# ZHSD-Power-Decoupling.net
KiCad netlist of a schematic drawn in Altium Designer
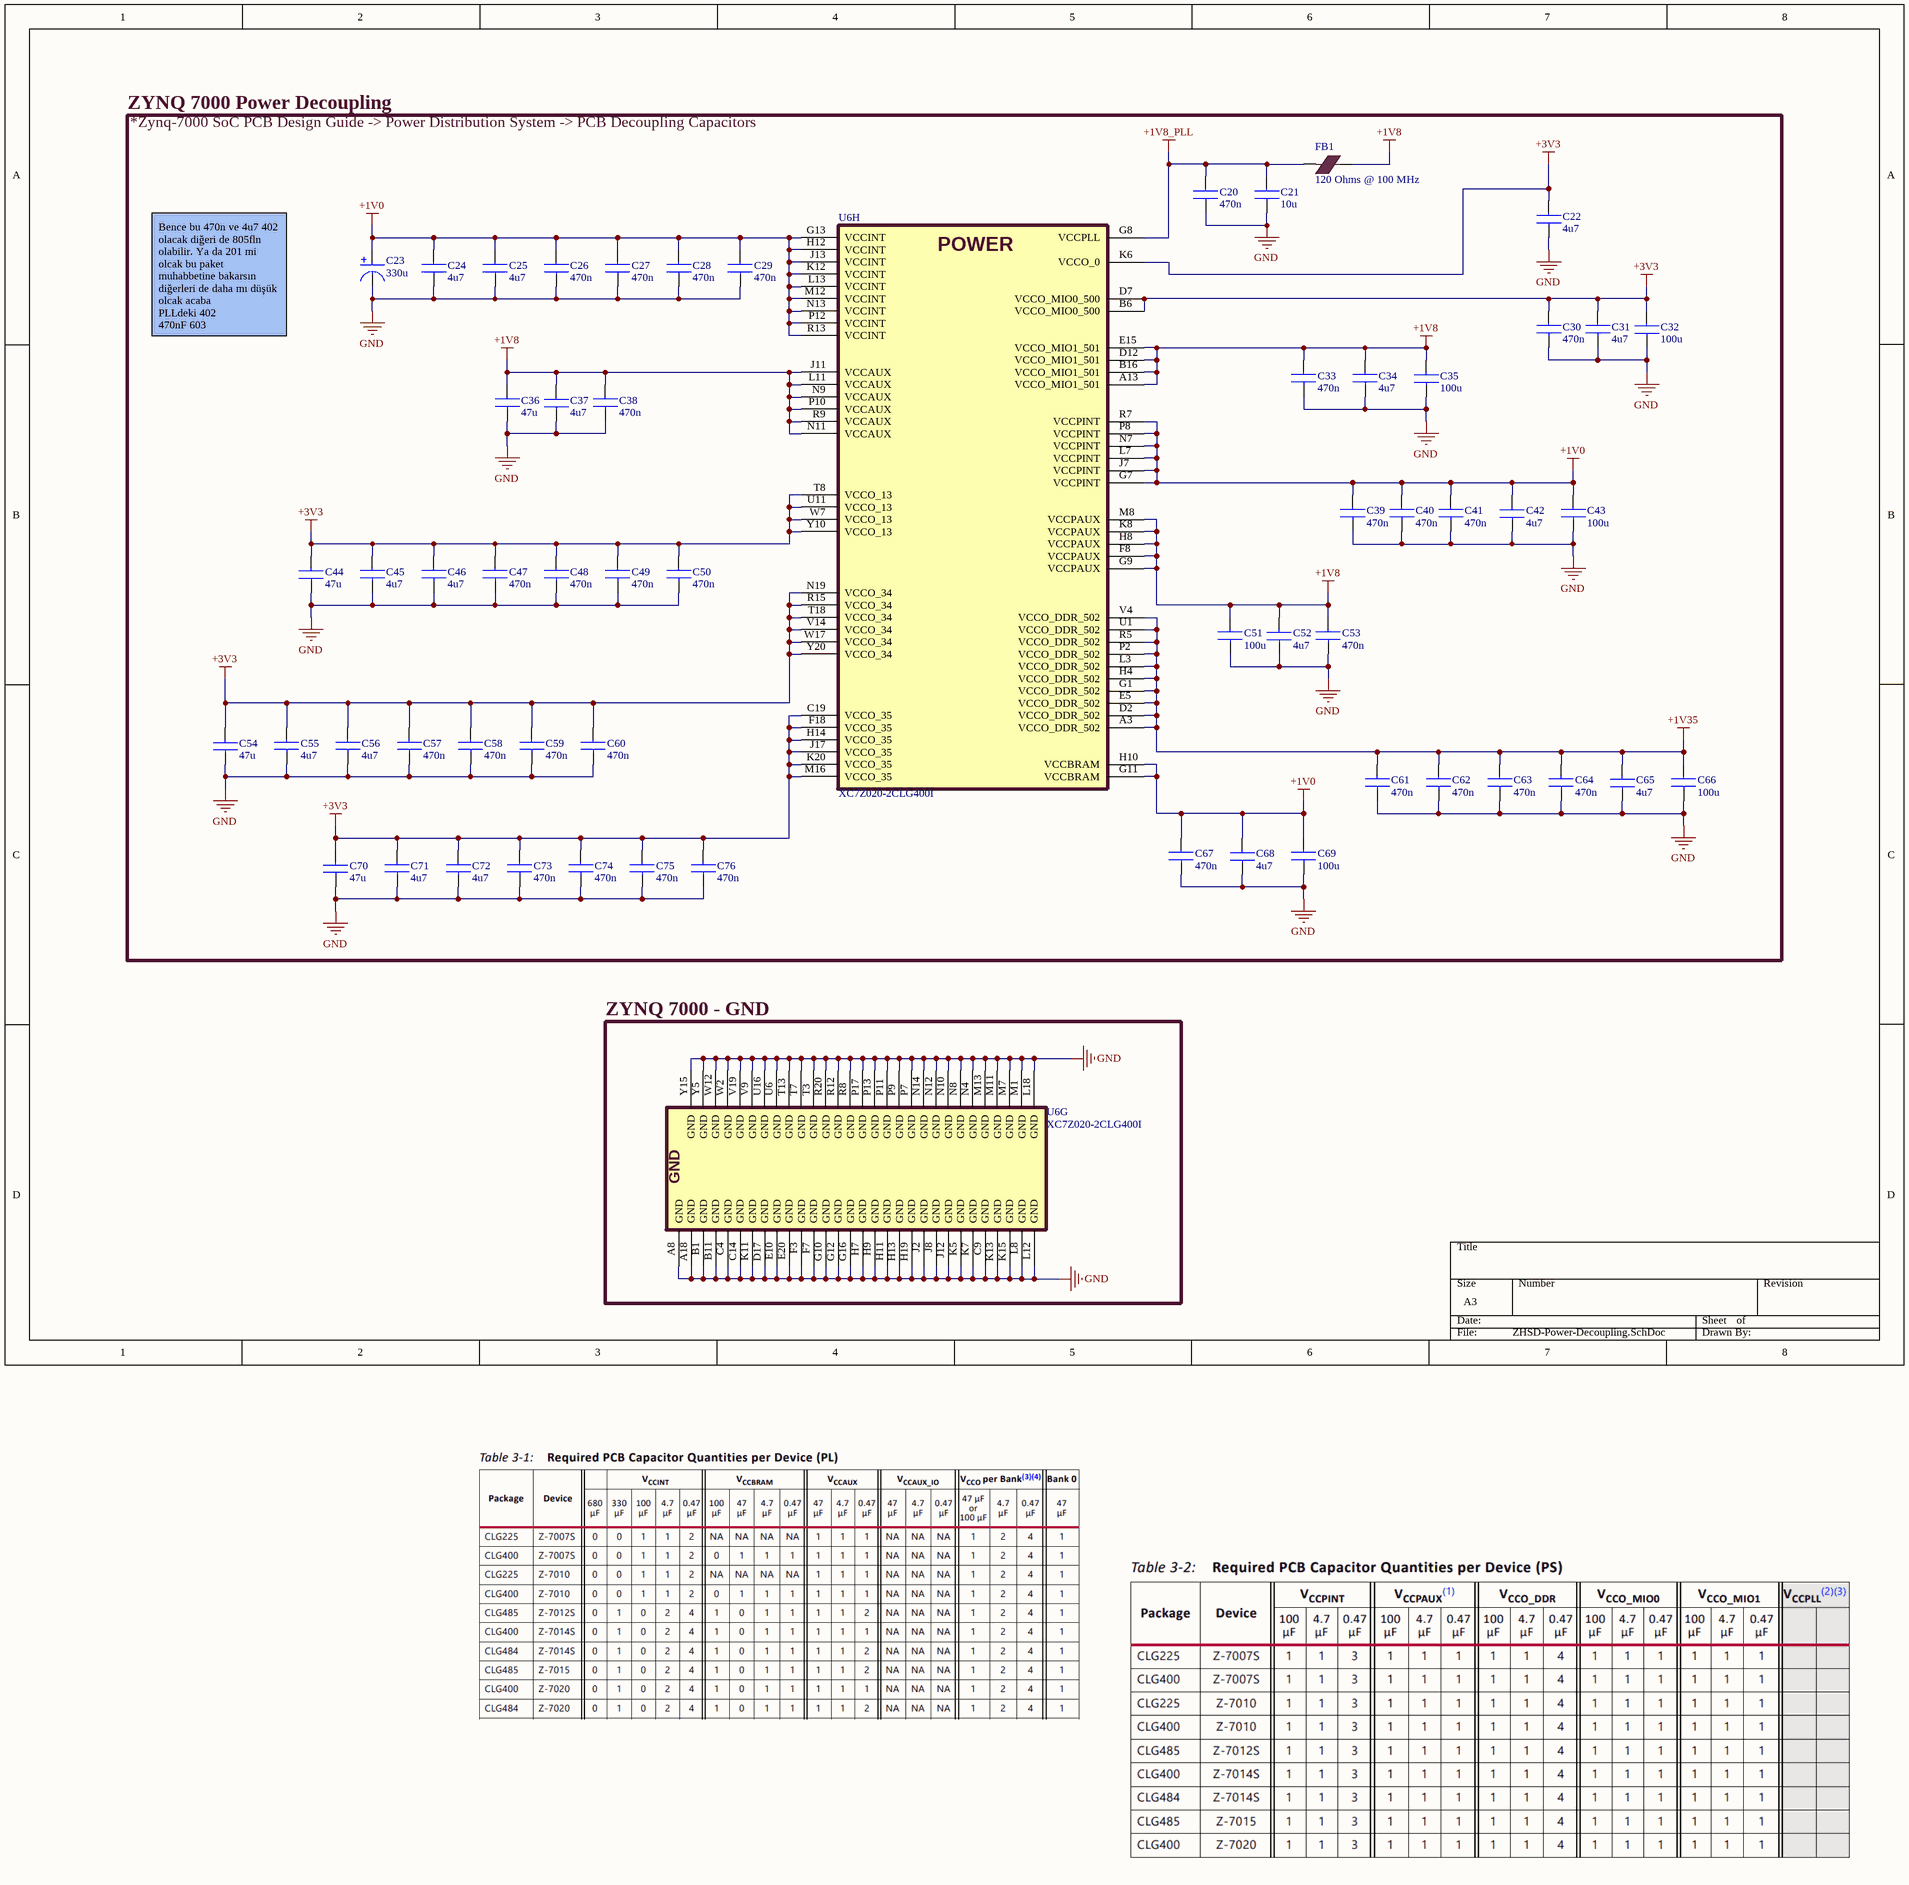
[diagram p0: ZHSD-Power-Decoupling.SchDoc]

(export (version "E")
  (design (tool "Eeschema 10.0.6"))
  (components
    (comp (ref "C20")
      (value "470n")
      (footprint "0402CAPC1005X06N")
      (description "CAP CER 0.47UF 6.3V X5R 0402(1005) ±10%")
      (fields (field (name "MANUFACTURER") "Murata Electronics") (field (name "MPN") "GRM155R60J474KE19D"))
      (libsource (lib "UK_Library") (part "GRM155R60J474KE19D"))
    )
    (comp (ref "C21")
      (value "10u")
      (footprint "0603CAPC1608X09N")
      (description "CAP CER 10UF 4V X5R 0603 (1608) ±20%")
      (fields (field (name "MANUFACTURER") "Murata Electronics") (field (name "MPN") "GRM188R60G106ME47D"))
      (libsource (lib "UK_Library") (part "GRM188R60G106ME47D"))
    )
    (comp (ref "C22")
      (value "4u7")
      (footprint "0805CAPC2012X14N")
      (description "CAP CER 4.7UF 10V X7R 0805 (2012) ±10%")
      (fields (field (name "MANUFACTURER") "Murata Electronics") (field (name "MPN") "GRM21BR71A475KE51L"))
      (libsource (lib "UK_Library") (part "GRM21BR71A475KE51L"))
    )
    (comp (ref "C23")
      (value "330u")
      (footprint "T525D337M006ATE025")
      (description "CAP TANT POLY 330UF 6.3V 2917 (7343) ±20%")
      (fields (field (name "MANUFACTURER") "KEMET") (field (name "MPN") "T525D337M006ATE025"))
      (libsource (lib "UK_Library") (part "T525D337M006ATE025"))
    )
    (comp (ref "C24")
      (value "4u7")
      (footprint "0805CAPC2012X14N")
      (description "CAP CER 4.7UF 10V X7R 0805 (2012) ±10%")
      (fields (field (name "MANUFACTURER") "Murata Electronics") (field (name "MPN") "GRM21BR71A475KE51L"))
      (libsource (lib "UK_Library") (part "GRM21BR71A475KE51L"))
    )
    (comp (ref "C25")
      (value "4u7")
      (footprint "0805CAPC2012X14N")
      (description "CAP CER 4.7UF 10V X7R 0805 (2012) ±10%")
      (fields (field (name "MANUFACTURER") "Murata Electronics") (field (name "MPN") "GRM21BR71A475KE51L"))
      (libsource (lib "UK_Library") (part "GRM21BR71A475KE51L"))
    )
    (comp (ref "C26")
      (value "470n")
      (footprint "0402CAPC1005X06N")
      (description "CAP CER 0.47UF 6.3V X5R 0402(1005) ±10%")
      (fields (field (name "MANUFACTURER") "Murata Electronics") (field (name "MPN") "GRM155R60J474KE19D"))
      (libsource (lib "UK_Library") (part "GRM155R60J474KE19D"))
    )
    (comp (ref "C27")
      (value "470n")
      (footprint "0402CAPC1005X06N")
      (description "CAP CER 0.47UF 6.3V X5R 0402(1005) ±10%")
      (fields (field (name "MANUFACTURER") "Murata Electronics") (field (name "MPN") "GRM155R60J474KE19D"))
      (libsource (lib "UK_Library") (part "GRM155R60J474KE19D"))
    )
    (comp (ref "C28")
      (value "470n")
      (footprint "0402CAPC1005X06N")
      (description "CAP CER 0.47UF 6.3V X5R 0402(1005) ±10%")
      (fields (field (name "MANUFACTURER") "Murata Electronics") (field (name "MPN") "GRM155R60J474KE19D"))
      (libsource (lib "UK_Library") (part "GRM155R60J474KE19D"))
    )
    (comp (ref "C29")
      (value "470n")
      (footprint "0402CAPC1005X06N")
      (description "CAP CER 0.47UF 6.3V X5R 0402(1005) ±10%")
      (fields (field (name "MANUFACTURER") "Murata Electronics") (field (name "MPN") "GRM155R60J474KE19D"))
      (libsource (lib "UK_Library") (part "GRM155R60J474KE19D"))
    )
    (comp (ref "C30")
      (value "470n")
      (footprint "0402CAPC1005X06N")
      (description "CAP CER 0.47UF 6.3V X5R 0402(1005) ±10%")
      (fields (field (name "MANUFACTURER") "Murata Electronics") (field (name "MPN") "GRM155R60J474KE19D"))
      (libsource (lib "UK_Library") (part "GRM155R60J474KE19D"))
    )
    (comp (ref "C31")
      (value "4u7")
      (footprint "0805CAPC2012X14N")
      (description "CAP CER 4.7UF 10V X7R 0805 (2012) ±10%")
      (fields (field (name "MANUFACTURER") "Murata Electronics") (field (name "MPN") "GRM21BR71A475KE51L"))
      (libsource (lib "UK_Library") (part "GRM21BR71A475KE51L"))
    )
    (comp (ref "C32")
      (value "100u")
      (footprint "1210CAPC3225X27N")
      (description "CAP CER 100UF 4V X7U 1210 (3225) ±20%")
      (fields (field (name "MANUFACTURER") "Murata Electronics") (field (name "MPN") "GRM32EE70G107ME19L"))
      (libsource (lib "UK_Library") (part "GRM32EE70G107ME19L"))
    )
    (comp (ref "C33")
      (value "470n")
      (footprint "0402CAPC1005X06N")
      (description "CAP CER 0.47UF 6.3V X5R 0402(1005) ±10%")
      (fields (field (name "MANUFACTURER") "Murata Electronics") (field (name "MPN") "GRM155R60J474KE19D"))
      (libsource (lib "UK_Library") (part "GRM155R60J474KE19D"))
    )
    (comp (ref "C34")
      (value "4u7")
      (footprint "0805CAPC2012X14N")
      (description "CAP CER 4.7UF 10V X7R 0805 (2012) ±10%")
      (fields (field (name "MANUFACTURER") "Murata Electronics") (field (name "MPN") "GRM21BR71A475KE51L"))
      (libsource (lib "UK_Library") (part "GRM21BR71A475KE51L"))
    )
    (comp (ref "C35")
      (value "100u")
      (footprint "1210CAPC3225X27N")
      (description "CAP CER 100UF 4V X7U 1210 (3225) ±20%")
      (fields (field (name "MANUFACTURER") "Murata Electronics") (field (name "MPN") "GRM32EE70G107ME19L"))
      (libsource (lib "UK_Library") (part "GRM32EE70G107ME19L"))
    )
    (comp (ref "C36")
      (value "47u")
      (footprint "1210CAPC3225X27N")
      (description "CAP CER 47UF 6.3V X7R 1210 1210 (3225) ±20%")
      (fields (field (name "MANUFACTURER") "Murata Electronics") (field (name "MPN") "GRM32ER70J476ME20L"))
      (libsource (lib "UK_Library") (part "GRM32ER70J476ME20L"))
    )
    (comp (ref "C37")
      (value "4u7")
      (footprint "0805CAPC2012X14N")
      (description "CAP CER 4.7UF 10V X7R 0805 (2012) ±10%")
      (fields (field (name "MANUFACTURER") "Murata Electronics") (field (name "MPN") "GRM21BR71A475KE51L"))
      (libsource (lib "UK_Library") (part "GRM21BR71A475KE51L"))
    )
    (comp (ref "C38")
      (value "470n")
      (footprint "0402CAPC1005X06N")
      (description "CAP CER 0.47UF 6.3V X5R 0402(1005) ±10%")
      (fields (field (name "MANUFACTURER") "Murata Electronics") (field (name "MPN") "GRM155R60J474KE19D"))
      (libsource (lib "UK_Library") (part "GRM155R60J474KE19D"))
    )
    (comp (ref "C39")
      (value "470n")
      (footprint "0402CAPC1005X06N")
      (description "CAP CER 0.47UF 6.3V X5R 0402(1005) ±10%")
      (fields (field (name "MANUFACTURER") "Murata Electronics") (field (name "MPN") "GRM155R60J474KE19D"))
      (libsource (lib "UK_Library") (part "GRM155R60J474KE19D"))
    )
    (comp (ref "C40")
      (value "470n")
      (footprint "0402CAPC1005X06N")
      (description "CAP CER 0.47UF 6.3V X5R 0402(1005) ±10%")
      (fields (field (name "MANUFACTURER") "Murata Electronics") (field (name "MPN") "GRM155R60J474KE19D"))
      (libsource (lib "UK_Library") (part "GRM155R60J474KE19D"))
    )
    (comp (ref "C41")
      (value "470n")
      (footprint "0603CAPC1608X09N")
      (description "CAP CER 0.47UF 6.3V X7R 0603 (1608) ±10%")
      (fields (field (name "MANUFACTURER") "Murata Electronics") (field (name "MPN") "GRM188R70J474KA01D"))
      (libsource (lib "UK_Library") (part "GRM188R70J474KA01D"))
    )
    (comp (ref "C42")
      (value "4u7")
      (footprint "0805CAPC2012X14N")
      (description "CAP CER 4.7UF 10V X7R 0805 (2012) ±10%")
      (fields (field (name "MANUFACTURER") "Murata Electronics") (field (name "MPN") "GRM21BR71A475KE51L"))
      (libsource (lib "UK_Library") (part "GRM21BR71A475KE51L"))
    )
    (comp (ref "C43")
      (value "100u")
      (footprint "1210CAPC3225X27N")
      (description "CAP CER 100UF 4V X7U 1210 (3225) ±20%")
      (fields (field (name "MANUFACTURER") "Murata Electronics") (field (name "MPN") "GRM32EE70G107ME19L"))
      (libsource (lib "UK_Library") (part "GRM32EE70G107ME19L"))
    )
    (comp (ref "C44")
      (value "47u")
      (footprint "1210CAPC3225X27N")
      (description "CAP CER 47UF 6.3V X7R 1210 1210 (3225) ±20%")
      (fields (field (name "MANUFACTURER") "Murata Electronics") (field (name "MPN") "GRM32ER70J476ME20L"))
      (libsource (lib "UK_Library") (part "GRM32ER70J476ME20L"))
    )
    (comp (ref "C45")
      (value "4u7")
      (footprint "0805CAPC2012X14N")
      (description "CAP CER 4.7UF 10V X7R 0805 (2012) ±10%")
      (fields (field (name "MANUFACTURER") "Murata Electronics") (field (name "MPN") "GRM21BR71A475KE51L"))
      (libsource (lib "UK_Library") (part "GRM21BR71A475KE51L"))
    )
    (comp (ref "C46")
      (value "4u7")
      (footprint "0805CAPC2012X14N")
      (description "CAP CER 4.7UF 10V X7R 0805 (2012) ±10%")
      (fields (field (name "MANUFACTURER") "Murata Electronics") (field (name "MPN") "GRM21BR71A475KE51L"))
      (libsource (lib "UK_Library") (part "GRM21BR71A475KE51L"))
    )
    (comp (ref "C47")
      (value "470n")
      (footprint "0402CAPC1005X06N")
      (description "CAP CER 0.47UF 6.3V X5R 0402(1005) ±10%")
      (fields (field (name "MANUFACTURER") "Murata Electronics") (field (name "MPN") "GRM155R60J474KE19D"))
      (libsource (lib "UK_Library") (part "GRM155R60J474KE19D"))
    )
    (comp (ref "C48")
      (value "470n")
      (footprint "0402CAPC1005X06N")
      (description "CAP CER 0.47UF 6.3V X5R 0402(1005) ±10%")
      (fields (field (name "MANUFACTURER") "Murata Electronics") (field (name "MPN") "GRM155R60J474KE19D"))
      (libsource (lib "UK_Library") (part "GRM155R60J474KE19D"))
    )
    (comp (ref "C49")
      (value "470n")
      (footprint "0402CAPC1005X06N")
      (description "CAP CER 0.47UF 6.3V X5R 0402(1005) ±10%")
      (fields (field (name "MANUFACTURER") "Murata Electronics") (field (name "MPN") "GRM155R60J474KE19D"))
      (libsource (lib "UK_Library") (part "GRM155R60J474KE19D"))
    )
    (comp (ref "C50")
      (value "470n")
      (footprint "0402CAPC1005X06N")
      (description "CAP CER 0.47UF 6.3V X5R 0402(1005) ±10%")
      (fields (field (name "MANUFACTURER") "Murata Electronics") (field (name "MPN") "GRM155R60J474KE19D"))
      (libsource (lib "UK_Library") (part "GRM155R60J474KE19D"))
    )
    (comp (ref "C51")
      (value "100u")
      (footprint "1210CAPC3225X27N")
      (description "CAP CER 100UF 4V X7U 1210 (3225) ±20%")
      (fields (field (name "MANUFACTURER") "Murata Electronics") (field (name "MPN") "GRM32EE70G107ME19L"))
      (libsource (lib "UK_Library") (part "GRM32EE70G107ME19L"))
    )
    (comp (ref "C52")
      (value "4u7")
      (footprint "0805CAPC2012X14N")
      (description "CAP CER 4.7UF 10V X7R 0805 (2012) ±10%")
      (fields (field (name "MANUFACTURER") "Murata Electronics") (field (name "MPN") "GRM21BR71A475KE51L"))
      (libsource (lib "UK_Library") (part "GRM21BR71A475KE51L"))
    )
    (comp (ref "C53")
      (value "470n")
      (footprint "0402CAPC1005X06N")
      (description "CAP CER 0.47UF 6.3V X5R 0402(1005) ±10%")
      (fields (field (name "MANUFACTURER") "Murata Electronics") (field (name "MPN") "GRM155R60J474KE19D"))
      (libsource (lib "UK_Library") (part "GRM155R60J474KE19D"))
    )
    (comp (ref "C54")
      (value "47u")
      (footprint "1210CAPC3225X27N")
      (description "CAP CER 47UF 6.3V X7R 1210 1210 (3225) ±20%")
      (fields (field (name "MANUFACTURER") "Murata Electronics") (field (name "MPN") "GRM32ER70J476ME20L"))
      (libsource (lib "UK_Library") (part "GRM32ER70J476ME20L"))
    )
    (comp (ref "C55")
      (value "4u7")
      (footprint "0805CAPC2012X14N")
      (description "CAP CER 4.7UF 10V X7R 0805 (2012) ±10%")
      (fields (field (name "MANUFACTURER") "Murata Electronics") (field (name "MPN") "GRM21BR71A475KE51L"))
      (libsource (lib "UK_Library") (part "GRM21BR71A475KE51L"))
    )
    (comp (ref "C56")
      (value "4u7")
      (footprint "0805CAPC2012X14N")
      (description "CAP CER 4.7UF 10V X7R 0805 (2012) ±10%")
      (fields (field (name "MANUFACTURER") "Murata Electronics") (field (name "MPN") "GRM21BR71A475KE51L"))
      (libsource (lib "UK_Library") (part "GRM21BR71A475KE51L"))
    )
    (comp (ref "C57")
      (value "470n")
      (footprint "0402CAPC1005X06N")
      (description "CAP CER 0.47UF 6.3V X5R 0402(1005) ±10%")
      (fields (field (name "MANUFACTURER") "Murata Electronics") (field (name "MPN") "GRM155R60J474KE19D"))
      (libsource (lib "UK_Library") (part "GRM155R60J474KE19D"))
    )
    (comp (ref "C58")
      (value "470n")
      (footprint "0402CAPC1005X06N")
      (description "CAP CER 0.47UF 6.3V X5R 0402(1005) ±10%")
      (fields (field (name "MANUFACTURER") "Murata Electronics") (field (name "MPN") "GRM155R60J474KE19D"))
      (libsource (lib "UK_Library") (part "GRM155R60J474KE19D"))
    )
    (comp (ref "C59")
      (value "470n")
      (footprint "0402CAPC1005X06N")
      (description "CAP CER 0.47UF 6.3V X5R 0402(1005) ±10%")
      (fields (field (name "MANUFACTURER") "Murata Electronics") (field (name "MPN") "GRM155R60J474KE19D"))
      (libsource (lib "UK_Library") (part "GRM155R60J474KE19D"))
    )
    (comp (ref "C60")
      (value "470n")
      (footprint "0402CAPC1005X06N")
      (description "CAP CER 0.47UF 6.3V X5R 0402(1005) ±10%")
      (fields (field (name "MANUFACTURER") "Murata Electronics") (field (name "MPN") "GRM155R60J474KE19D"))
      (libsource (lib "UK_Library") (part "GRM155R60J474KE19D"))
    )
    (comp (ref "C61")
      (value "470n")
      (footprint "0402CAPC1005X06N")
      (description "CAP CER 0.47UF 6.3V X5R 0402(1005) ±10%")
      (fields (field (name "MANUFACTURER") "Murata Electronics") (field (name "MPN") "GRM155R60J474KE19D"))
      (libsource (lib "UK_Library") (part "GRM155R60J474KE19D"))
    )
    (comp (ref "C62")
      (value "470n")
      (footprint "0402CAPC1005X06N")
      (description "CAP CER 0.47UF 6.3V X5R 0402(1005) ±10%")
      (fields (field (name "MANUFACTURER") "Murata Electronics") (field (name "MPN") "GRM155R60J474KE19D"))
      (libsource (lib "UK_Library") (part "GRM155R60J474KE19D"))
    )
    (comp (ref "C63")
      (value "470n")
      (footprint "0402CAPC1005X06N")
      (description "CAP CER 0.47UF 6.3V X5R 0402(1005) ±10%")
      (fields (field (name "MANUFACTURER") "Murata Electronics") (field (name "MPN") "GRM155R60J474KE19D"))
      (libsource (lib "UK_Library") (part "GRM155R60J474KE19D"))
    )
    (comp (ref "C64")
      (value "470n")
      (footprint "0402CAPC1005X06N")
      (description "CAP CER 0.47UF 6.3V X5R 0402(1005) ±10%")
      (fields (field (name "MANUFACTURER") "Murata Electronics") (field (name "MPN") "GRM155R60J474KE19D"))
      (libsource (lib "UK_Library") (part "GRM155R60J474KE19D"))
    )
    (comp (ref "C65")
      (value "4u7")
      (footprint "0805CAPC2012X14N")
      (description "CAP CER 4.7UF 10V X7R 0805 (2012) ±10%")
      (fields (field (name "MANUFACTURER") "Murata Electronics") (field (name "MPN") "GRM21BR71A475KE51L"))
      (libsource (lib "UK_Library") (part "GRM21BR71A475KE51L"))
    )
    (comp (ref "C66")
      (value "100u")
      (footprint "1210CAPC3225X27N")
      (description "CAP CER 100UF 4V X7U 1210 (3225) ±20%")
      (fields (field (name "MANUFACTURER") "Murata Electronics") (field (name "MPN") "GRM32EE70G107ME19L"))
      (libsource (lib "UK_Library") (part "GRM32EE70G107ME19L"))
    )
    (comp (ref "C67")
      (value "470n")
      (footprint "0402CAPC1005X06N")
      (description "CAP CER 0.47UF 6.3V X5R 0402(1005) ±10%")
      (fields (field (name "MANUFACTURER") "Murata Electronics") (field (name "MPN") "GRM155R60J474KE19D"))
      (libsource (lib "UK_Library") (part "GRM155R60J474KE19D"))
    )
    (comp (ref "C68")
      (value "4u7")
      (footprint "0805CAPC2012X14N")
      (description "CAP CER 4.7UF 10V X7R 0805 (2012) ±10%")
      (fields (field (name "MANUFACTURER") "Murata Electronics") (field (name "MPN") "GRM21BR71A475KE51L"))
      (libsource (lib "UK_Library") (part "GRM21BR71A475KE51L"))
    )
    (comp (ref "C69")
      (value "100u")
      (footprint "1210CAPC3225X27N")
      (description "CAP CER 100UF 4V X7U 1210 (3225) ±20%")
      (fields (field (name "MANUFACTURER") "Murata Electronics") (field (name "MPN") "GRM32EE70G107ME19L"))
      (libsource (lib "UK_Library") (part "GRM32EE70G107ME19L"))
    )
    (comp (ref "C70")
      (value "47u")
      (footprint "1210CAPC3225X27N")
      (description "CAP CER 47UF 6.3V X7R 1210 1210 (3225) ±20%")
      (fields (field (name "MANUFACTURER") "Murata Electronics") (field (name "MPN") "GRM32ER70J476ME20L"))
      (libsource (lib "UK_Library") (part "GRM32ER70J476ME20L"))
    )
    (comp (ref "C71")
      (value "4u7")
      (footprint "0805CAPC2012X14N")
      (description "CAP CER 4.7UF 10V X7R 0805 (2012) ±10%")
      (fields (field (name "MANUFACTURER") "Murata Electronics") (field (name "MPN") "GRM21BR71A475KE51L"))
      (libsource (lib "UK_Library") (part "GRM21BR71A475KE51L"))
    )
    (comp (ref "C72")
      (value "4u7")
      (footprint "0805CAPC2012X14N")
      (description "CAP CER 4.7UF 10V X7R 0805 (2012) ±10%")
      (fields (field (name "MANUFACTURER") "Murata Electronics") (field (name "MPN") "GRM21BR71A475KE51L"))
      (libsource (lib "UK_Library") (part "GRM21BR71A475KE51L"))
    )
    (comp (ref "C73")
      (value "470n")
      (footprint "0402CAPC1005X06N")
      (description "CAP CER 0.47UF 6.3V X5R 0402(1005) ±10%")
      (fields (field (name "MANUFACTURER") "Murata Electronics") (field (name "MPN") "GRM155R60J474KE19D"))
      (libsource (lib "UK_Library") (part "GRM155R60J474KE19D"))
    )
    (comp (ref "C74")
      (value "470n")
      (footprint "0402CAPC1005X06N")
      (description "CAP CER 0.47UF 6.3V X5R 0402(1005) ±10%")
      (fields (field (name "MANUFACTURER") "Murata Electronics") (field (name "MPN") "GRM155R60J474KE19D"))
      (libsource (lib "UK_Library") (part "GRM155R60J474KE19D"))
    )
    (comp (ref "C75")
      (value "470n")
      (footprint "0402CAPC1005X06N")
      (description "CAP CER 0.47UF 6.3V X5R 0402(1005) ±10%")
      (fields (field (name "MANUFACTURER") "Murata Electronics") (field (name "MPN") "GRM155R60J474KE19D"))
      (libsource (lib "UK_Library") (part "GRM155R60J474KE19D"))
    )
    (comp (ref "C76")
      (value "470n")
      (footprint "0402CAPC1005X06N")
      (description "CAP CER 0.47UF 6.3V X5R 0402(1005) ±10%")
      (fields (field (name "MANUFACTURER") "Murata Electronics") (field (name "MPN") "GRM155R60J474KE19D"))
      (libsource (lib "UK_Library") (part "GRM155R60J474KE19D"))
    )
    (comp (ref "FB1")
      (value "120 Ohms @ 100 MHz")
      (footprint "0603INDC1608X08N")
      (description "FERRITE BEAD 120 OHM 0603 (1608) 3A 25mOhm")
      (fields (field (name "MANUFACTURER") "Murata Electronics") (field (name "MPN") "BLM18SG121TN1D"))
      (libsource (lib "UK_Library") (part "BLM18SG121TN1D"))
    )
    (comp (ref "U6")
      (value "XC7Z020-2CLG400I")
      (footprint "BGA400C80P20X20_1700X1700X147")
      (fields (field (name "MANUFACTURER") "AMD/XILINX"))
      (libsource (lib "UK_Library_SCH") (part "XC7Z020-2CLG400I"))
    )
  )
  (nets
    (net (code "1") (name "+1V0") (class "Default")
      (node (ref "C23") (pin "1") (pinfunction "1_1") (pintype "passive"))
      (node (ref "C24") (pin "2") (pinfunction "2_2") (pintype "passive"))
      (node (ref "C25") (pin "2") (pinfunction "2_2") (pintype "passive"))
      (node (ref "C26") (pin "2") (pinfunction "2_2") (pintype "passive"))
      (node (ref "C27") (pin "2") (pinfunction "2_2") (pintype "passive"))
      (node (ref "C28") (pin "2") (pinfunction "2_2") (pintype "passive"))
      (node (ref "C29") (pin "2") (pinfunction "2_2") (pintype "passive"))
      (node (ref "C39") (pin "2") (pinfunction "2_2") (pintype "passive"))
      (node (ref "C40") (pin "2") (pinfunction "2_2") (pintype "passive"))
      (node (ref "C41") (pin "2") (pinfunction "2_2") (pintype "passive"))
      (node (ref "C42") (pin "2") (pinfunction "2_2") (pintype "passive"))
      (node (ref "C43") (pin "1") (pinfunction "1_1") (pintype "passive"))
      (node (ref "C67") (pin "2") (pinfunction "2_2") (pintype "passive"))
      (node (ref "C68") (pin "2") (pinfunction "2_2") (pintype "passive"))
      (node (ref "C69") (pin "1") (pinfunction "1_1") (pintype "passive"))
      (node (ref "U6") (pin "G11") (pinfunction "VCCBRAM_G11") (pintype "power_in"))
      (node (ref "U6") (pin "G13") (pinfunction "VCCINT_G13") (pintype "power_in"))
      (node (ref "U6") (pin "G7") (pinfunction "VCCPINT_G7") (pintype "power_in"))
      (node (ref "U6") (pin "H10") (pinfunction "VCCBRAM_H10") (pintype "power_in"))
      (node (ref "U6") (pin "H12") (pinfunction "VCCINT_H12") (pintype "power_in"))
      (node (ref "U6") (pin "J13") (pinfunction "VCCINT_J13") (pintype "power_in"))
      (node (ref "U6") (pin "J7") (pinfunction "VCCPINT_J7") (pintype "power_in"))
      (node (ref "U6") (pin "K12") (pinfunction "VCCINT_K12") (pintype "power_in"))
      (node (ref "U6") (pin "L13") (pinfunction "VCCINT_L13") (pintype "power_in"))
      (node (ref "U6") (pin "L7") (pinfunction "VCCPINT_L7") (pintype "power_in"))
      (node (ref "U6") (pin "M12") (pinfunction "VCCINT_M12") (pintype "power_in"))
      (node (ref "U6") (pin "N13") (pinfunction "VCCINT_N13") (pintype "power_in"))
      (node (ref "U6") (pin "N7") (pinfunction "VCCPINT_N7") (pintype "power_in"))
      (node (ref "U6") (pin "P12") (pinfunction "VCCINT_P12") (pintype "power_in"))
      (node (ref "U6") (pin "P8") (pinfunction "VCCPINT_P8") (pintype "power_in"))
      (node (ref "U6") (pin "R13") (pinfunction "VCCINT_R13") (pintype "power_in"))
      (node (ref "U6") (pin "R7") (pinfunction "VCCPINT_R7") (pintype "power_in"))
    )
    (net (code "2") (name "+1V8") (class "Default")
      (node (ref "C33") (pin "2") (pinfunction "2_2") (pintype "passive"))
      (node (ref "C34") (pin "2") (pinfunction "2_2") (pintype "passive"))
      (node (ref "C35") (pin "1") (pinfunction "1_1") (pintype "passive"))
      (node (ref "C36") (pin "2") (pinfunction "2_2") (pintype "passive"))
      (node (ref "C37") (pin "2") (pinfunction "2_2") (pintype "passive"))
      (node (ref "C38") (pin "2") (pinfunction "2_2") (pintype "passive"))
      (node (ref "C51") (pin "1") (pinfunction "1_1") (pintype "passive"))
      (node (ref "C52") (pin "2") (pinfunction "2_2") (pintype "passive"))
      (node (ref "C53") (pin "2") (pinfunction "2_2") (pintype "passive"))
      (node (ref "FB1") (pin "2") (pinfunction "2_2") (pintype "passive"))
      (node (ref "U6") (pin "A13") (pinfunction "VCCO_MIO1_501_A13") (pintype "power_in"))
      (node (ref "U6") (pin "B16") (pinfunction "VCCO_MIO1_501_B16") (pintype "power_in"))
      (node (ref "U6") (pin "D12") (pinfunction "VCCO_MIO1_501_D12") (pintype "power_in"))
      (node (ref "U6") (pin "E15") (pinfunction "VCCO_MIO1_501_E15") (pintype "power_in"))
      (node (ref "U6") (pin "F8") (pinfunction "VCCPAUX_F8") (pintype "power_in"))
      (node (ref "U6") (pin "G9") (pinfunction "VCCPAUX_G9") (pintype "power_in"))
      (node (ref "U6") (pin "H8") (pinfunction "VCCPAUX_H8") (pintype "power_in"))
      (node (ref "U6") (pin "J11") (pinfunction "VCCAUX_J11") (pintype "power_in"))
      (node (ref "U6") (pin "K8") (pinfunction "VCCPAUX_K8") (pintype "power_in"))
      (node (ref "U6") (pin "L11") (pinfunction "VCCAUX_L11") (pintype "power_in"))
      (node (ref "U6") (pin "M8") (pinfunction "VCCPAUX_M8") (pintype "power_in"))
      (node (ref "U6") (pin "N11") (pinfunction "VCCAUX_N11") (pintype "power_in"))
      (node (ref "U6") (pin "N9") (pinfunction "VCCAUX_N9") (pintype "power_in"))
      (node (ref "U6") (pin "P10") (pinfunction "VCCAUX_P10") (pintype "power_in"))
      (node (ref "U6") (pin "R9") (pinfunction "VCCAUX_R9") (pintype "power_in"))
    )
    (net (code "3") (name "+1V8_PLL") (class "Default")
      (node (ref "C20") (pin "2") (pinfunction "2_2") (pintype "passive"))
      (node (ref "C21") (pin "2") (pinfunction "2_2") (pintype "passive"))
      (node (ref "FB1") (pin "1") (pinfunction "1_1") (pintype "passive"))
      (node (ref "U6") (pin "G8") (pinfunction "VCCPLL_G8") (pintype "power_in"))
    )
    (net (code "4") (name "+1V35") (class "Default")
      (node (ref "C61") (pin "2") (pinfunction "2_2") (pintype "passive"))
      (node (ref "C62") (pin "2") (pinfunction "2_2") (pintype "passive"))
      (node (ref "C63") (pin "2") (pinfunction "2_2") (pintype "passive"))
      (node (ref "C64") (pin "2") (pinfunction "2_2") (pintype "passive"))
      (node (ref "C65") (pin "2") (pinfunction "2_2") (pintype "passive"))
      (node (ref "C66") (pin "1") (pinfunction "1_1") (pintype "passive"))
      (node (ref "U6") (pin "A3") (pinfunction "VCCO_DDR_502_A3") (pintype "power_in"))
      (node (ref "U6") (pin "D2") (pinfunction "VCCO_DDR_502_D2") (pintype "power_in"))
      (node (ref "U6") (pin "E5") (pinfunction "VCCO_DDR_502_E5") (pintype "power_in"))
      (node (ref "U6") (pin "G1") (pinfunction "VCCO_DDR_502_G1") (pintype "power_in"))
      (node (ref "U6") (pin "H4") (pinfunction "VCCO_DDR_502_H4") (pintype "power_in"))
      (node (ref "U6") (pin "L3") (pinfunction "VCCO_DDR_502_L3") (pintype "power_in"))
      (node (ref "U6") (pin "P2") (pinfunction "VCCO_DDR_502_P2") (pintype "power_in"))
      (node (ref "U6") (pin "R5") (pinfunction "VCCO_DDR_502_R5") (pintype "power_in"))
      (node (ref "U6") (pin "U1") (pinfunction "VCCO_DDR_502_U1") (pintype "power_in"))
      (node (ref "U6") (pin "V4") (pinfunction "VCCO_DDR_502_V4") (pintype "power_in"))
    )
    (net (code "5") (name "+3V3") (class "Default")
      (node (ref "C22") (pin "2") (pinfunction "2_2") (pintype "passive"))
      (node (ref "C30") (pin "2") (pinfunction "2_2") (pintype "passive"))
      (node (ref "C31") (pin "2") (pinfunction "2_2") (pintype "passive"))
      (node (ref "C32") (pin "1") (pinfunction "1_1") (pintype "passive"))
      (node (ref "C44") (pin "2") (pinfunction "2_2") (pintype "passive"))
      (node (ref "C45") (pin "2") (pinfunction "2_2") (pintype "passive"))
      (node (ref "C46") (pin "2") (pinfunction "2_2") (pintype "passive"))
      (node (ref "C47") (pin "2") (pinfunction "2_2") (pintype "passive"))
      (node (ref "C48") (pin "2") (pinfunction "2_2") (pintype "passive"))
      (node (ref "C49") (pin "2") (pinfunction "2_2") (pintype "passive"))
      (node (ref "C50") (pin "2") (pinfunction "2_2") (pintype "passive"))
      (node (ref "C54") (pin "2") (pinfunction "2_2") (pintype "passive"))
      (node (ref "C55") (pin "2") (pinfunction "2_2") (pintype "passive"))
      (node (ref "C56") (pin "2") (pinfunction "2_2") (pintype "passive"))
      (node (ref "C57") (pin "2") (pinfunction "2_2") (pintype "passive"))
      (node (ref "C58") (pin "2") (pinfunction "2_2") (pintype "passive"))
      (node (ref "C59") (pin "2") (pinfunction "2_2") (pintype "passive"))
      (node (ref "C60") (pin "2") (pinfunction "2_2") (pintype "passive"))
      (node (ref "C70") (pin "2") (pinfunction "2_2") (pintype "passive"))
      (node (ref "C71") (pin "2") (pinfunction "2_2") (pintype "passive"))
      (node (ref "C72") (pin "2") (pinfunction "2_2") (pintype "passive"))
      (node (ref "C73") (pin "2") (pinfunction "2_2") (pintype "passive"))
      (node (ref "C74") (pin "2") (pinfunction "2_2") (pintype "passive"))
      (node (ref "C75") (pin "2") (pinfunction "2_2") (pintype "passive"))
      (node (ref "C76") (pin "2") (pinfunction "2_2") (pintype "passive"))
      (node (ref "U6") (pin "B6") (pinfunction "VCCO_MIO0_500_B6") (pintype "power_in"))
      (node (ref "U6") (pin "C19") (pinfunction "VCCO_35_C19") (pintype "power_in"))
      (node (ref "U6") (pin "D7") (pinfunction "VCCO_MIO0_500_D7") (pintype "power_in"))
      (node (ref "U6") (pin "F18") (pinfunction "VCCO_35_F18") (pintype "power_in"))
      (node (ref "U6") (pin "H14") (pinfunction "VCCO_35_H14") (pintype "power_in"))
      (node (ref "U6") (pin "J17") (pinfunction "VCCO_35_J17") (pintype "power_in"))
      (node (ref "U6") (pin "K20") (pinfunction "VCCO_35_K20") (pintype "power_in"))
      (node (ref "U6") (pin "K6") (pinfunction "VCCO_0_K6") (pintype "power_in"))
      (node (ref "U6") (pin "M16") (pinfunction "VCCO_35_M16") (pintype "power_in"))
      (node (ref "U6") (pin "N19") (pinfunction "VCCO_34_N19") (pintype "power_in"))
      (node (ref "U6") (pin "R15") (pinfunction "VCCO_34_R15") (pintype "power_in"))
      (node (ref "U6") (pin "T18") (pinfunction "VCCO_34_T18") (pintype "power_in"))
      (node (ref "U6") (pin "T8") (pinfunction "VCCO_13_T8") (pintype "power_in"))
      (node (ref "U6") (pin "U11") (pinfunction "VCCO_13_U11") (pintype "power_in"))
      (node (ref "U6") (pin "V14") (pinfunction "VCCO_34_V14") (pintype "power_in"))
      (node (ref "U6") (pin "W17") (pinfunction "VCCO_34_W17") (pintype "power_in"))
      (node (ref "U6") (pin "W7") (pinfunction "VCCO_13_W7") (pintype "power_in"))
      (node (ref "U6") (pin "Y10") (pinfunction "VCCO_13_Y10") (pintype "power_in"))
      (node (ref "U6") (pin "Y20") (pinfunction "VCCO_34_Y20") (pintype "power_in"))
    )
    (net (code "6") (name "GND") (class "Default")
      (node (ref "C20") (pin "1") (pinfunction "1_1") (pintype "passive"))
      (node (ref "C21") (pin "1") (pinfunction "1_1") (pintype "passive"))
      (node (ref "C22") (pin "1") (pinfunction "1_1") (pintype "passive"))
      (node (ref "C23") (pin "2") (pinfunction "2_2") (pintype "passive"))
      (node (ref "C24") (pin "1") (pinfunction "1_1") (pintype "passive"))
      (node (ref "C25") (pin "1") (pinfunction "1_1") (pintype "passive"))
      (node (ref "C26") (pin "1") (pinfunction "1_1") (pintype "passive"))
      (node (ref "C27") (pin "1") (pinfunction "1_1") (pintype "passive"))
      (node (ref "C28") (pin "1") (pinfunction "1_1") (pintype "passive"))
      (node (ref "C29") (pin "1") (pinfunction "1_1") (pintype "passive"))
      (node (ref "C30") (pin "1") (pinfunction "1_1") (pintype "passive"))
      (node (ref "C31") (pin "1") (pinfunction "1_1") (pintype "passive"))
      (node (ref "C32") (pin "2") (pinfunction "2_2") (pintype "passive"))
      (node (ref "C33") (pin "1") (pinfunction "1_1") (pintype "passive"))
      (node (ref "C34") (pin "1") (pinfunction "1_1") (pintype "passive"))
      (node (ref "C35") (pin "2") (pinfunction "2_2") (pintype "passive"))
      (node (ref "C36") (pin "1") (pinfunction "1_1") (pintype "passive"))
      (node (ref "C37") (pin "1") (pinfunction "1_1") (pintype "passive"))
      (node (ref "C38") (pin "1") (pinfunction "1_1") (pintype "passive"))
      (node (ref "C39") (pin "1") (pinfunction "1_1") (pintype "passive"))
      (node (ref "C40") (pin "1") (pinfunction "1_1") (pintype "passive"))
      (node (ref "C41") (pin "1") (pinfunction "1_1") (pintype "passive"))
      (node (ref "C42") (pin "1") (pinfunction "1_1") (pintype "passive"))
      (node (ref "C43") (pin "2") (pinfunction "2_2") (pintype "passive"))
      (node (ref "C44") (pin "1") (pinfunction "1_1") (pintype "passive"))
      (node (ref "C45") (pin "1") (pinfunction "1_1") (pintype "passive"))
      (node (ref "C46") (pin "1") (pinfunction "1_1") (pintype "passive"))
      (node (ref "C47") (pin "1") (pinfunction "1_1") (pintype "passive"))
      (node (ref "C48") (pin "1") (pinfunction "1_1") (pintype "passive"))
      (node (ref "C49") (pin "1") (pinfunction "1_1") (pintype "passive"))
      (node (ref "C50") (pin "1") (pinfunction "1_1") (pintype "passive"))
      (node (ref "C51") (pin "2") (pinfunction "2_2") (pintype "passive"))
      (node (ref "C52") (pin "1") (pinfunction "1_1") (pintype "passive"))
      (node (ref "C53") (pin "1") (pinfunction "1_1") (pintype "passive"))
      (node (ref "C54") (pin "1") (pinfunction "1_1") (pintype "passive"))
      (node (ref "C55") (pin "1") (pinfunction "1_1") (pintype "passive"))
      (node (ref "C56") (pin "1") (pinfunction "1_1") (pintype "passive"))
      (node (ref "C57") (pin "1") (pinfunction "1_1") (pintype "passive"))
      (node (ref "C58") (pin "1") (pinfunction "1_1") (pintype "passive"))
      (node (ref "C59") (pin "1") (pinfunction "1_1") (pintype "passive"))
      (node (ref "C60") (pin "1") (pinfunction "1_1") (pintype "passive"))
      (node (ref "C61") (pin "1") (pinfunction "1_1") (pintype "passive"))
      (node (ref "C62") (pin "1") (pinfunction "1_1") (pintype "passive"))
      (node (ref "C63") (pin "1") (pinfunction "1_1") (pintype "passive"))
      (node (ref "C64") (pin "1") (pinfunction "1_1") (pintype "passive"))
      (node (ref "C65") (pin "1") (pinfunction "1_1") (pintype "passive"))
      (node (ref "C66") (pin "2") (pinfunction "2_2") (pintype "passive"))
      (node (ref "C67") (pin "1") (pinfunction "1_1") (pintype "passive"))
      (node (ref "C68") (pin "1") (pinfunction "1_1") (pintype "passive"))
      (node (ref "C69") (pin "2") (pinfunction "2_2") (pintype "passive"))
      (node (ref "C70") (pin "1") (pinfunction "1_1") (pintype "passive"))
      (node (ref "C71") (pin "1") (pinfunction "1_1") (pintype "passive"))
      (node (ref "C72") (pin "1") (pinfunction "1_1") (pintype "passive"))
      (node (ref "C73") (pin "1") (pinfunction "1_1") (pintype "passive"))
      (node (ref "C74") (pin "1") (pinfunction "1_1") (pintype "passive"))
      (node (ref "C75") (pin "1") (pinfunction "1_1") (pintype "passive"))
      (node (ref "C76") (pin "1") (pinfunction "1_1") (pintype "passive"))
      (node (ref "U6") (pin "A18") (pinfunction "GND_A18") (pintype "power_in"))
      (node (ref "U6") (pin "A8") (pinfunction "GND_A8") (pintype "power_in"))
      (node (ref "U6") (pin "B1") (pinfunction "GND_B1") (pintype "power_in"))
      (node (ref "U6") (pin "B11") (pinfunction "GND_B11") (pintype "power_in"))
      (node (ref "U6") (pin "C14") (pinfunction "GND_C14") (pintype "power_in"))
      (node (ref "U6") (pin "C4") (pinfunction "GND_C4") (pintype "power_in"))
      (node (ref "U6") (pin "C9") (pinfunction "GND_C9") (pintype "power_in"))
      (node (ref "U6") (pin "D17") (pinfunction "GND_D17") (pintype "power_in"))
      (node (ref "U6") (pin "E10") (pinfunction "GND_E10") (pintype "power_in"))
      (node (ref "U6") (pin "E20") (pinfunction "GND_E20") (pintype "power_in"))
      (node (ref "U6") (pin "F3") (pinfunction "GND_F3") (pintype "power_in"))
      (node (ref "U6") (pin "F7") (pinfunction "GND_F7") (pintype "power_in"))
      (node (ref "U6") (pin "G10") (pinfunction "GND_G10") (pintype "power_in"))
      (node (ref "U6") (pin "G12") (pinfunction "GND_G12") (pintype "power_in"))
      (node (ref "U6") (pin "G16") (pinfunction "GND_G16") (pintype "power_in"))
      (node (ref "U6") (pin "H11") (pinfunction "GND_H11") (pintype "power_in"))
      (node (ref "U6") (pin "H13") (pinfunction "GND_H13") (pintype "power_in"))
      (node (ref "U6") (pin "H19") (pinfunction "GND_H19") (pintype "power_in"))
      (node (ref "U6") (pin "H7") (pinfunction "GND_H7") (pintype "power_in"))
      (node (ref "U6") (pin "H9") (pinfunction "GND_H9") (pintype "power_in"))
      (node (ref "U6") (pin "J12") (pinfunction "GND_J12") (pintype "power_in"))
      (node (ref "U6") (pin "J2") (pinfunction "GND_J2") (pintype "power_in"))
      (node (ref "U6") (pin "J8") (pinfunction "GND_J8") (pintype "power_in"))
      (node (ref "U6") (pin "K11") (pinfunction "GND_K11") (pintype "power_in"))
      (node (ref "U6") (pin "K13") (pinfunction "GND_K13") (pintype "power_in"))
      (node (ref "U6") (pin "K15") (pinfunction "GND_K15") (pintype "power_in"))
      (node (ref "U6") (pin "K5") (pinfunction "GND_K5") (pintype "power_in"))
      (node (ref "U6") (pin "K7") (pinfunction "GND_K7") (pintype "power_in"))
      (node (ref "U6") (pin "L12") (pinfunction "GND_L12") (pintype "power_in"))
      (node (ref "U6") (pin "L18") (pinfunction "GND_L18") (pintype "power_in"))
      (node (ref "U6") (pin "L8") (pinfunction "GND_L8") (pintype "power_in"))
      (node (ref "U6") (pin "M1") (pinfunction "GND_M1") (pintype "power_in"))
      (node (ref "U6") (pin "M11") (pinfunction "GND_M11") (pintype "power_in"))
      (node (ref "U6") (pin "M13") (pinfunction "GND_M13") (pintype "power_in"))
      (node (ref "U6") (pin "M7") (pinfunction "GND_M7") (pintype "power_in"))
      (node (ref "U6") (pin "N10") (pinfunction "GND_N10") (pintype "power_in"))
      (node (ref "U6") (pin "N12") (pinfunction "GND_N12") (pintype "power_in"))
      (node (ref "U6") (pin "N14") (pinfunction "GND_N14") (pintype "power_in"))
      (node (ref "U6") (pin "N4") (pinfunction "GND_N4") (pintype "power_in"))
      (node (ref "U6") (pin "N8") (pinfunction "GND_N8") (pintype "power_in"))
      (node (ref "U6") (pin "P11") (pinfunction "GND_P11") (pintype "power_in"))
      (node (ref "U6") (pin "P13") (pinfunction "GND_P13") (pintype "power_in"))
      (node (ref "U6") (pin "P17") (pinfunction "GND_P17") (pintype "power_in"))
      (node (ref "U6") (pin "P7") (pinfunction "GND_P7") (pintype "power_in"))
      (node (ref "U6") (pin "P9") (pinfunction "GND_P9") (pintype "power_in"))
      (node (ref "U6") (pin "R12") (pinfunction "GND_R12") (pintype "power_in"))
      (node (ref "U6") (pin "R20") (pinfunction "GND_R20") (pintype "power_in"))
      (node (ref "U6") (pin "R8") (pinfunction "GND_R8") (pintype "power_in"))
      (node (ref "U6") (pin "T13") (pinfunction "GND_T13") (pintype "power_in"))
      (node (ref "U6") (pin "T3") (pinfunction "GND_T3") (pintype "power_in"))
      (node (ref "U6") (pin "T7") (pinfunction "GND_T7") (pintype "power_in"))
      (node (ref "U6") (pin "U16") (pinfunction "GND_U16") (pintype "power_in"))
      (node (ref "U6") (pin "U6") (pinfunction "GND_U6") (pintype "power_in"))
      (node (ref "U6") (pin "V19") (pinfunction "GND_V19") (pintype "power_in"))
      (node (ref "U6") (pin "V9") (pinfunction "GND_V9") (pintype "power_in"))
      (node (ref "U6") (pin "W12") (pinfunction "GND_W12") (pintype "power_in"))
      (node (ref "U6") (pin "W2") (pinfunction "GND_W2") (pintype "power_in"))
      (node (ref "U6") (pin "Y15") (pinfunction "GND_Y15") (pintype "power_in"))
      (node (ref "U6") (pin "Y5") (pinfunction "GND_Y5") (pintype "power_in"))
    )
  )
)
